# StripController1.net
KiCad netlist of a schematic drawn in EAGLE
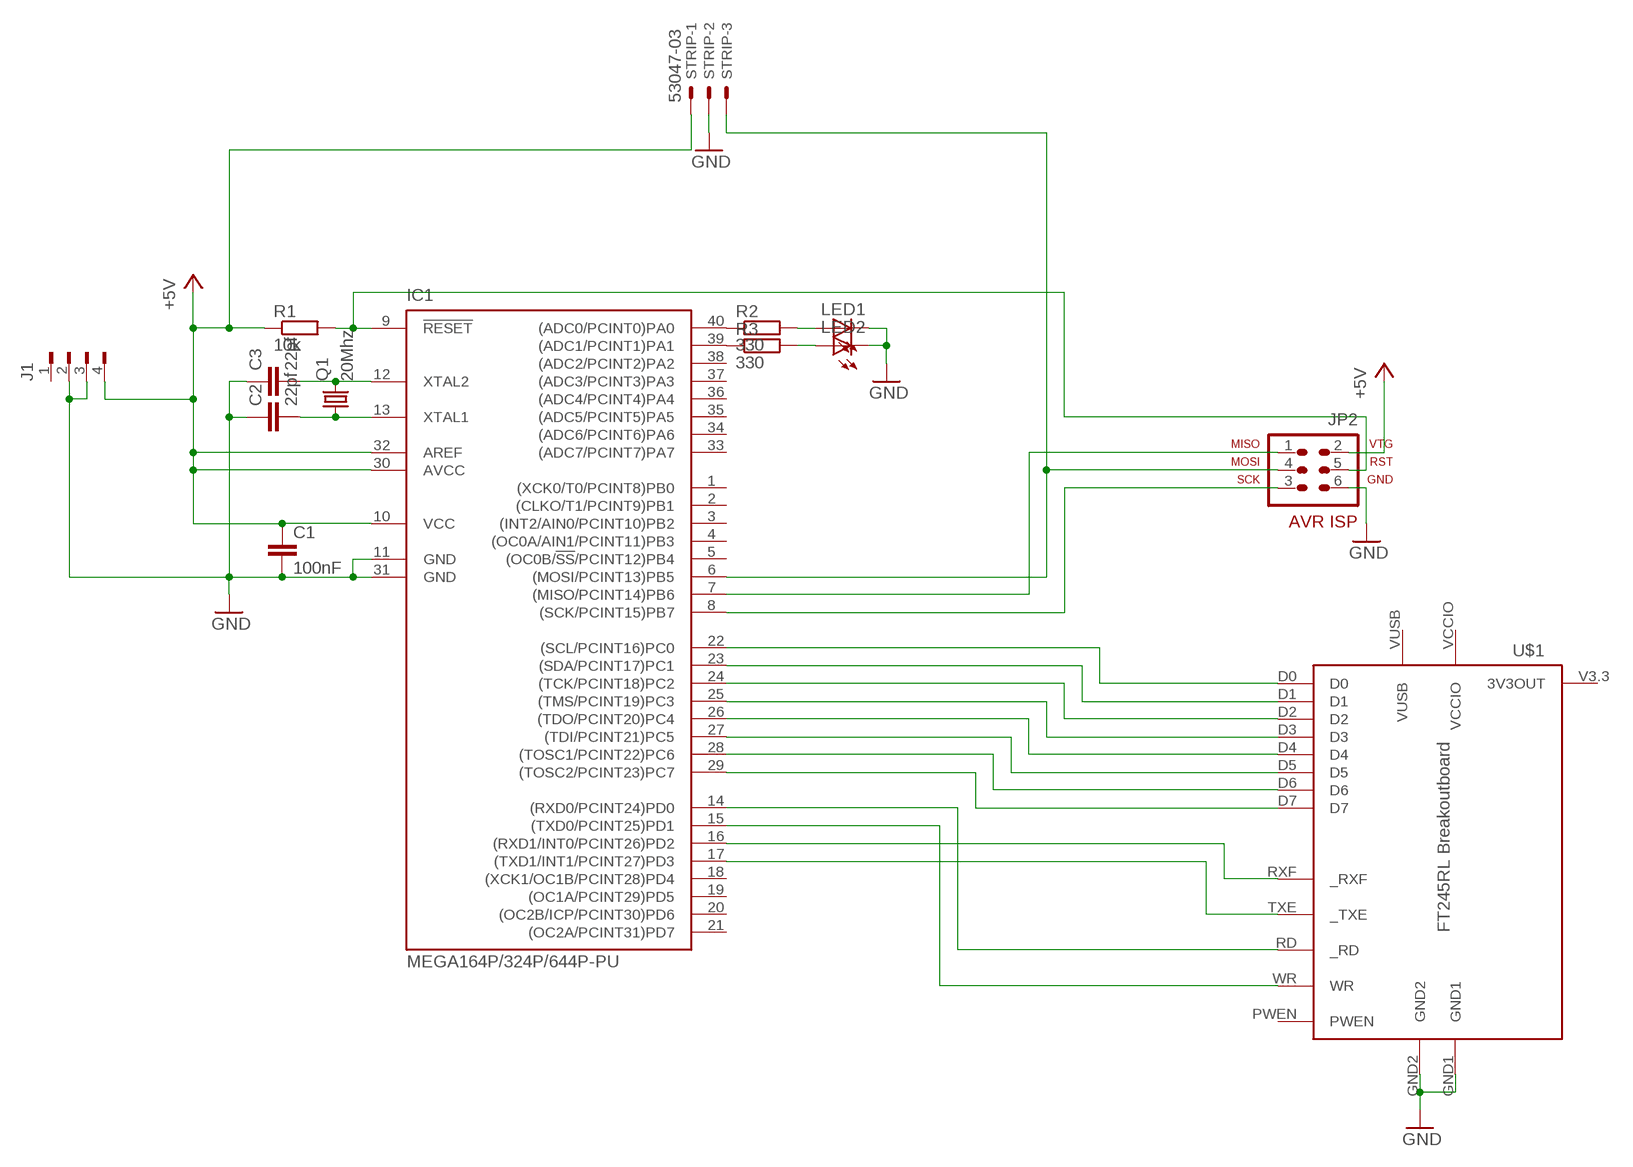
[diagram p0: schematic, sheet 1]

(export (version "E")
  (design (tool "Eeschema 10.0.6"))
  (components
    (comp (ref "C1")
      (value "100nF")
      (footprint "eagle-import:C050-030X075")
      (libsource (lib "eagle-import") (part "C-EU050-030X075"))
    )
    (comp (ref "C2")
      (value "22pf")
      (footprint "eagle-import:C050-024X044")
      (libsource (lib "eagle-import") (part "C-EU050-024X044"))
    )
    (comp (ref "C3")
      (value "22pf")
      (footprint "eagle-import:C050-024X044")
      (libsource (lib "eagle-import") (part "C-EU050-024X044"))
    )
    (comp (ref "IC1")
      (value "MEGA164P/324P/644P-PU")
      (footprint "eagle-import:DIL40")
      (libsource (lib "eagle-import") (part "MEGA164P/324P/644P-PU"))
    )
    (comp (ref "J1")
      (value "FLOPPY-4")
      (footprint "eagle-import:FLOPPY-4")
      (libsource (lib "eagle-import") (part "FLOPPY-4"))
    )
    (comp (ref "JP2")
      (value "AVR-ISP-6")
      (footprint "eagle-import:AVR-ISP-6")
      (libsource (lib "eagle-import") (part "AVR-ISP-6"))
    )
    (comp (ref "LED1")
      (value "LED3MM")
      (footprint "eagle-import:LED3MM")
      (libsource (lib "eagle-import") (part "LED3MM"))
    )
    (comp (ref "LED2")
      (value "LED3MM")
      (footprint "eagle-import:LED3MM")
      (libsource (lib "eagle-import") (part "LED3MM"))
    )
    (comp (ref "Q1")
      (value "20Mhz")
      (footprint "eagle-import:HC49U70")
      (libsource (lib "eagle-import") (part "CRYSTALHC49U70"))
    )
    (comp (ref "R1")
      (value "10k")
      (footprint "eagle-import:0207_10")
      (libsource (lib "eagle-import") (part "R-EU_0207/10"))
    )
    (comp (ref "R2")
      (value "330")
      (footprint "eagle-import:0207_10")
      (libsource (lib "eagle-import") (part "R-EU_0207/10"))
    )
    (comp (ref "R3")
      (value "330")
      (footprint "eagle-import:0207_10")
      (libsource (lib "eagle-import") (part "R-EU_0207/10"))
    )
    (comp (ref "STRIP")
      (value "53047-03")
      (footprint "eagle-import:53047-03")
      (fields (field (name "MPN") "530470310"))
      (libsource (lib "eagle-import") (part "53?-03047"))
    )
    (comp (ref "U$1")
      (value "FT245RL_BREAKOUTBOARD")
      (footprint "eagle-import:SPARKFUN_FT245RL_BOARD")
      (libsource (lib "eagle-import") (part "FT245RL_BREAKOUTBOARD"))
    )
  )
  (nets
    (net (code "1") (name "+5V") (class "Default")
      (node (ref "C1") (pin "1") (pinfunction "1_1") (pintype "passive"))
      (node (ref "IC1") (pin "10") (pinfunction "VCC_10") (pintype "power_in"))
      (node (ref "IC1") (pin "30") (pinfunction "AVCC_30") (pintype "power_in"))
      (node (ref "IC1") (pin "32") (pinfunction "AREF_32") (pintype "power_in"))
      (node (ref "J1") (pin "4") (pinfunction "4_4") (pintype "passive"))
      (node (ref "JP2") (pin "2") (pinfunction "2_2") (pintype "passive"))
      (node (ref "R1") (pin "1") (pinfunction "1_1") (pintype "passive"))
      (node (ref "STRIP") (pin "1") (pinfunction "S_1") (pintype "passive"))
    )
    (net (code "2") (name "/VCCIO") (class "Default")
      (node (ref "U$1") (pin "VCCIO") (pinfunction "VCCIO_VCCIO") (pintype "power_in"))
    )
    (net (code "3") (name "GND") (class "Default")
      (node (ref "C1") (pin "2") (pinfunction "2_2") (pintype "passive"))
      (node (ref "C2") (pin "1") (pinfunction "1_1") (pintype "passive"))
      (node (ref "C3") (pin "1") (pinfunction "1_1") (pintype "passive"))
      (node (ref "IC1") (pin "11") (pinfunction "GND_11") (pintype "power_in"))
      (node (ref "IC1") (pin "31") (pinfunction "GND_31") (pintype "power_in"))
      (node (ref "J1") (pin "2") (pinfunction "2_2") (pintype "passive"))
      (node (ref "J1") (pin "3") (pinfunction "3_3") (pintype "passive"))
      (node (ref "JP2") (pin "6") (pinfunction "6_6") (pintype "passive"))
      (node (ref "LED1") (pin "K") (pinfunction "C_K") (pintype "passive"))
      (node (ref "LED2") (pin "K") (pinfunction "C_K") (pintype "passive"))
      (node (ref "STRIP") (pin "2") (pinfunction "S_2") (pintype "passive"))
      (node (ref "U$1") (pin "GND1") (pinfunction "GND1_GND1") (pintype "power_in"))
      (node (ref "U$1") (pin "GND2") (pinfunction "GND2_GND2") (pintype "power_in"))
    )
    (net (code "4") (name "Net-(IC1-(ADC0{slash}PCINT0)PA0)") (class "Default")
      (node (ref "IC1") (pin "40") (pinfunction "(ADC0/PCINT0)PA0_40") (pintype "bidirectional"))
      (node (ref "R2") (pin "1") (pinfunction "1_1") (pintype "passive"))
    )
    (net (code "5") (name "Net-(IC1-(ADC1{slash}PCINT1)PA1)") (class "Default")
      (node (ref "IC1") (pin "39") (pinfunction "(ADC1/PCINT1)PA1_39") (pintype "bidirectional"))
      (node (ref "R3") (pin "1") (pinfunction "1_1") (pintype "passive"))
    )
    (net (code "6") (name "Net-(IC1-(MISO{slash}PCINT14)PB6)") (class "Default")
      (node (ref "IC1") (pin "7") (pinfunction "(MISO/PCINT14)PB6_7") (pintype "bidirectional"))
      (node (ref "JP2") (pin "1") (pinfunction "1_1") (pintype "passive"))
    )
    (net (code "7") (name "Net-(IC1-(MOSI{slash}PCINT13)PB5)") (class "Default")
      (node (ref "IC1") (pin "6") (pinfunction "(MOSI/PCINT13)PB5_6") (pintype "bidirectional"))
      (node (ref "JP2") (pin "4") (pinfunction "4_4") (pintype "passive"))
      (node (ref "STRIP") (pin "3") (pinfunction "S_3") (pintype "passive"))
    )
    (net (code "8") (name "Net-(IC1-(RXD0{slash}PCINT24)PD0)") (class "Default")
      (node (ref "IC1") (pin "14") (pinfunction "(RXD0/PCINT24)PD0_14") (pintype "bidirectional"))
      (node (ref "U$1") (pin "RD") (pinfunction "_RD_RD") (pintype "bidirectional"))
    )
    (net (code "9") (name "Net-(IC1-(RXD1{slash}INT0{slash}PCINT26)PD2)") (class "Default")
      (node (ref "IC1") (pin "16") (pinfunction "(RXD1/INT0/PCINT26)PD2_16") (pintype "bidirectional"))
      (node (ref "U$1") (pin "RXF") (pinfunction "_RXF_RXF") (pintype "bidirectional"))
    )
    (net (code "10") (name "Net-(IC1-(SCK{slash}PCINT15)PB7)") (class "Default")
      (node (ref "IC1") (pin "8") (pinfunction "(SCK/PCINT15)PB7_8") (pintype "bidirectional"))
      (node (ref "JP2") (pin "3") (pinfunction "3_3") (pintype "passive"))
    )
    (net (code "11") (name "Net-(IC1-(SCL{slash}PCINT16)PC0)") (class "Default")
      (node (ref "IC1") (pin "22") (pinfunction "(SCL/PCINT16)PC0_22") (pintype "bidirectional"))
      (node (ref "U$1") (pin "D0") (pinfunction "D0_D0") (pintype "output"))
    )
    (net (code "12") (name "Net-(IC1-(SDA{slash}PCINT17)PC1)") (class "Default")
      (node (ref "IC1") (pin "23") (pinfunction "(SDA/PCINT17)PC1_23") (pintype "bidirectional"))
      (node (ref "U$1") (pin "D1") (pinfunction "D1_D1") (pintype "input"))
    )
    (net (code "13") (name "Net-(IC1-(TCK{slash}PCINT18)PC2)") (class "Default")
      (node (ref "IC1") (pin "24") (pinfunction "(TCK/PCINT18)PC2_24") (pintype "bidirectional"))
      (node (ref "U$1") (pin "D2") (pinfunction "D2_D2") (pintype "output"))
    )
    (net (code "14") (name "Net-(IC1-(TDI{slash}PCINT21)PC5)") (class "Default")
      (node (ref "IC1") (pin "27") (pinfunction "(TDI/PCINT21)PC5_27") (pintype "bidirectional"))
      (node (ref "U$1") (pin "D5") (pinfunction "D5_D5") (pintype "input"))
    )
    (net (code "15") (name "Net-(IC1-(TDO{slash}PCINT20)PC4)") (class "Default")
      (node (ref "IC1") (pin "26") (pinfunction "(TDO/PCINT20)PC4_26") (pintype "bidirectional"))
      (node (ref "U$1") (pin "D4") (pinfunction "D4_D4") (pintype "output"))
    )
    (net (code "16") (name "Net-(IC1-(TMS{slash}PCINT19)PC3)") (class "Default")
      (node (ref "IC1") (pin "25") (pinfunction "(TMS/PCINT19)PC3_25") (pintype "bidirectional"))
      (node (ref "U$1") (pin "D3") (pinfunction "D3_D3") (pintype "input"))
    )
    (net (code "17") (name "Net-(IC1-(TOSC1{slash}PCINT22)PC6)") (class "Default")
      (node (ref "IC1") (pin "28") (pinfunction "(TOSC1/PCINT22)PC6_28") (pintype "bidirectional"))
      (node (ref "U$1") (pin "D6") (pinfunction "D6_D6") (pintype "input"))
    )
    (net (code "18") (name "Net-(IC1-(TOSC2{slash}PCINT23)PC7)") (class "Default")
      (node (ref "IC1") (pin "29") (pinfunction "(TOSC2/PCINT23)PC7_29") (pintype "bidirectional"))
      (node (ref "U$1") (pin "D7") (pinfunction "D7_D7") (pintype "input"))
    )
    (net (code "19") (name "Net-(IC1-(TXD0{slash}PCINT25)PD1)") (class "Default")
      (node (ref "IC1") (pin "15") (pinfunction "(TXD0/PCINT25)PD1_15") (pintype "bidirectional"))
      (node (ref "U$1") (pin "WR") (pinfunction "WR_WR") (pintype "bidirectional"))
    )
    (net (code "20") (name "Net-(IC1-(TXD1{slash}INT1{slash}PCINT27)PD3)") (class "Default")
      (node (ref "IC1") (pin "17") (pinfunction "(TXD1/INT1/PCINT27)PD3_17") (pintype "bidirectional"))
      (node (ref "U$1") (pin "TXE") (pinfunction "_TXE_TXE") (pintype "bidirectional"))
    )
    (net (code "21") (name "Net-(IC1-XTAL1)") (class "Default")
      (node (ref "C2") (pin "2") (pinfunction "2_2") (pintype "passive"))
      (node (ref "IC1") (pin "13") (pinfunction "XTAL1_13") (pintype "input"))
      (node (ref "Q1") (pin "1") (pinfunction "1_1") (pintype "passive"))
    )
    (net (code "22") (name "Net-(IC1-XTAL2)") (class "Default")
      (node (ref "C3") (pin "2") (pinfunction "2_2") (pintype "passive"))
      (node (ref "IC1") (pin "12") (pinfunction "XTAL2_12") (pintype "output"))
      (node (ref "Q1") (pin "2") (pinfunction "2_2") (pintype "passive"))
    )
    (net (code "23") (name "Net-(IC1-~{RESET})") (class "Default")
      (node (ref "IC1") (pin "9") (pinfunction "~{RESET}_9") (pintype "input"))
      (node (ref "JP2") (pin "5") (pinfunction "5_5") (pintype "passive"))
      (node (ref "R1") (pin "2") (pinfunction "2_2") (pintype "passive"))
    )
    (net (code "24") (name "Net-(LED1-PadA)") (class "Default")
      (node (ref "LED1") (pin "A") (pinfunction "A_A") (pintype "passive"))
      (node (ref "R2") (pin "2") (pinfunction "2_2") (pintype "passive"))
    )
    (net (code "25") (name "Net-(LED2-PadA)") (class "Default")
      (node (ref "LED2") (pin "A") (pinfunction "A_A") (pintype "passive"))
      (node (ref "R3") (pin "2") (pinfunction "2_2") (pintype "passive"))
    )
    (net (code "26") (name "unconnected-(IC1-(ADC2{slash}PCINT2)PA2-Pad38)") (class "Default")
      (node (ref "IC1") (pin "38") (pinfunction "(ADC2/PCINT2)PA2_38") (pintype "bidirectional"))
    )
    (net (code "27") (name "unconnected-(IC1-(ADC3{slash}PCINT3)PA3-Pad37)") (class "Default")
      (node (ref "IC1") (pin "37") (pinfunction "(ADC3/PCINT3)PA3_37") (pintype "bidirectional"))
    )
    (net (code "28") (name "unconnected-(IC1-(ADC4{slash}PCINT4)PA4-Pad36)") (class "Default")
      (node (ref "IC1") (pin "36") (pinfunction "(ADC4/PCINT4)PA4_36") (pintype "bidirectional"))
    )
    (net (code "29") (name "unconnected-(IC1-(ADC5{slash}PCINT5)PA5-Pad35)") (class "Default")
      (node (ref "IC1") (pin "35") (pinfunction "(ADC5/PCINT5)PA5_35") (pintype "bidirectional"))
    )
    (net (code "30") (name "unconnected-(IC1-(ADC6{slash}PCINT6)PA6-Pad34)") (class "Default")
      (node (ref "IC1") (pin "34") (pinfunction "(ADC6/PCINT6)PA6_34") (pintype "bidirectional"))
    )
    (net (code "31") (name "unconnected-(IC1-(ADC7{slash}PCINT7)PA7-Pad33)") (class "Default")
      (node (ref "IC1") (pin "33") (pinfunction "(ADC7/PCINT7)PA7_33") (pintype "bidirectional"))
    )
    (net (code "32") (name "unconnected-(IC1-(CLKO{slash}T1{slash}PCINT9)PB1-Pad2)") (class "Default")
      (node (ref "IC1") (pin "2") (pinfunction "(CLKO/T1/PCINT9)PB1_2") (pintype "bidirectional"))
    )
    (net (code "33") (name "unconnected-(IC1-(INT2{slash}AIN0{slash}PCINT10)PB2-Pad3)") (class "Default")
      (node (ref "IC1") (pin "3") (pinfunction "(INT2/AIN0/PCINT10)PB2_3") (pintype "bidirectional"))
    )
    (net (code "34") (name "unconnected-(IC1-(OC0A{slash}AIN1{slash}PCINT11)PB3-Pad4)") (class "Default")
      (node (ref "IC1") (pin "4") (pinfunction "(OC0A/AIN1/PCINT11)PB3_4") (pintype "bidirectional"))
    )
    (net (code "35") (name "unconnected-(IC1-(OC0B{slash}~{SS}{slash}PCINT12)PB4-Pad5)") (class "Default")
      (node (ref "IC1") (pin "5") (pinfunction "(OC0B/~{SS}/PCINT12)PB4_5") (pintype "bidirectional"))
    )
    (net (code "36") (name "unconnected-(IC1-(OC1A{slash}PCINT29)PD5-Pad19)") (class "Default")
      (node (ref "IC1") (pin "19") (pinfunction "(OC1A/PCINT29)PD5_19") (pintype "bidirectional"))
    )
    (net (code "37") (name "unconnected-(IC1-(OC2A{slash}PCINT31)PD7-Pad21)") (class "Default")
      (node (ref "IC1") (pin "21") (pinfunction "(OC2A/PCINT31)PD7_21") (pintype "bidirectional"))
    )
    (net (code "38") (name "unconnected-(IC1-(OC2B{slash}ICP{slash}PCINT30)PD6-Pad20)") (class "Default")
      (node (ref "IC1") (pin "20") (pinfunction "(OC2B/ICP/PCINT30)PD6_20") (pintype "bidirectional"))
    )
    (net (code "39") (name "unconnected-(IC1-(XCK0{slash}T0{slash}PCINT8)PB0-Pad1)") (class "Default")
      (node (ref "IC1") (pin "1") (pinfunction "(XCK0/T0/PCINT8)PB0_1") (pintype "bidirectional"))
    )
    (net (code "40") (name "unconnected-(IC1-(XCK1{slash}OC1B{slash}PCINT28)PD4-Pad18)") (class "Default")
      (node (ref "IC1") (pin "18") (pinfunction "(XCK1/OC1B/PCINT28)PD4_18") (pintype "bidirectional"))
    )
    (net (code "41") (name "unconnected-(J1-Pad1)") (class "Default")
      (node (ref "J1") (pin "1") (pinfunction "1_1") (pintype "passive"))
    )
    (net (code "42") (name "unconnected-(U$1-3V3OUT-PadV3.3)") (class "Default")
      (node (ref "U$1") (pin "V3.3") (pinfunction "3V3OUT_V3.3") (pintype "output"))
    )
    (net (code "43") (name "unconnected-(U$1-PadPWEN)") (class "Default")
      (node (ref "U$1") (pin "PWEN") (pinfunction "PWEN_PWEN") (pintype "bidirectional"))
    )
    (net (code "44") (name "unconnected-(U$1-PadVUSB)") (class "Default")
      (node (ref "U$1") (pin "VUSB") (pinfunction "VUSB_VUSB") (pintype "bidirectional"))
    )
  )
)
